# STLINK.net
KiCad netlist of a schematic drawn in Altium Designer
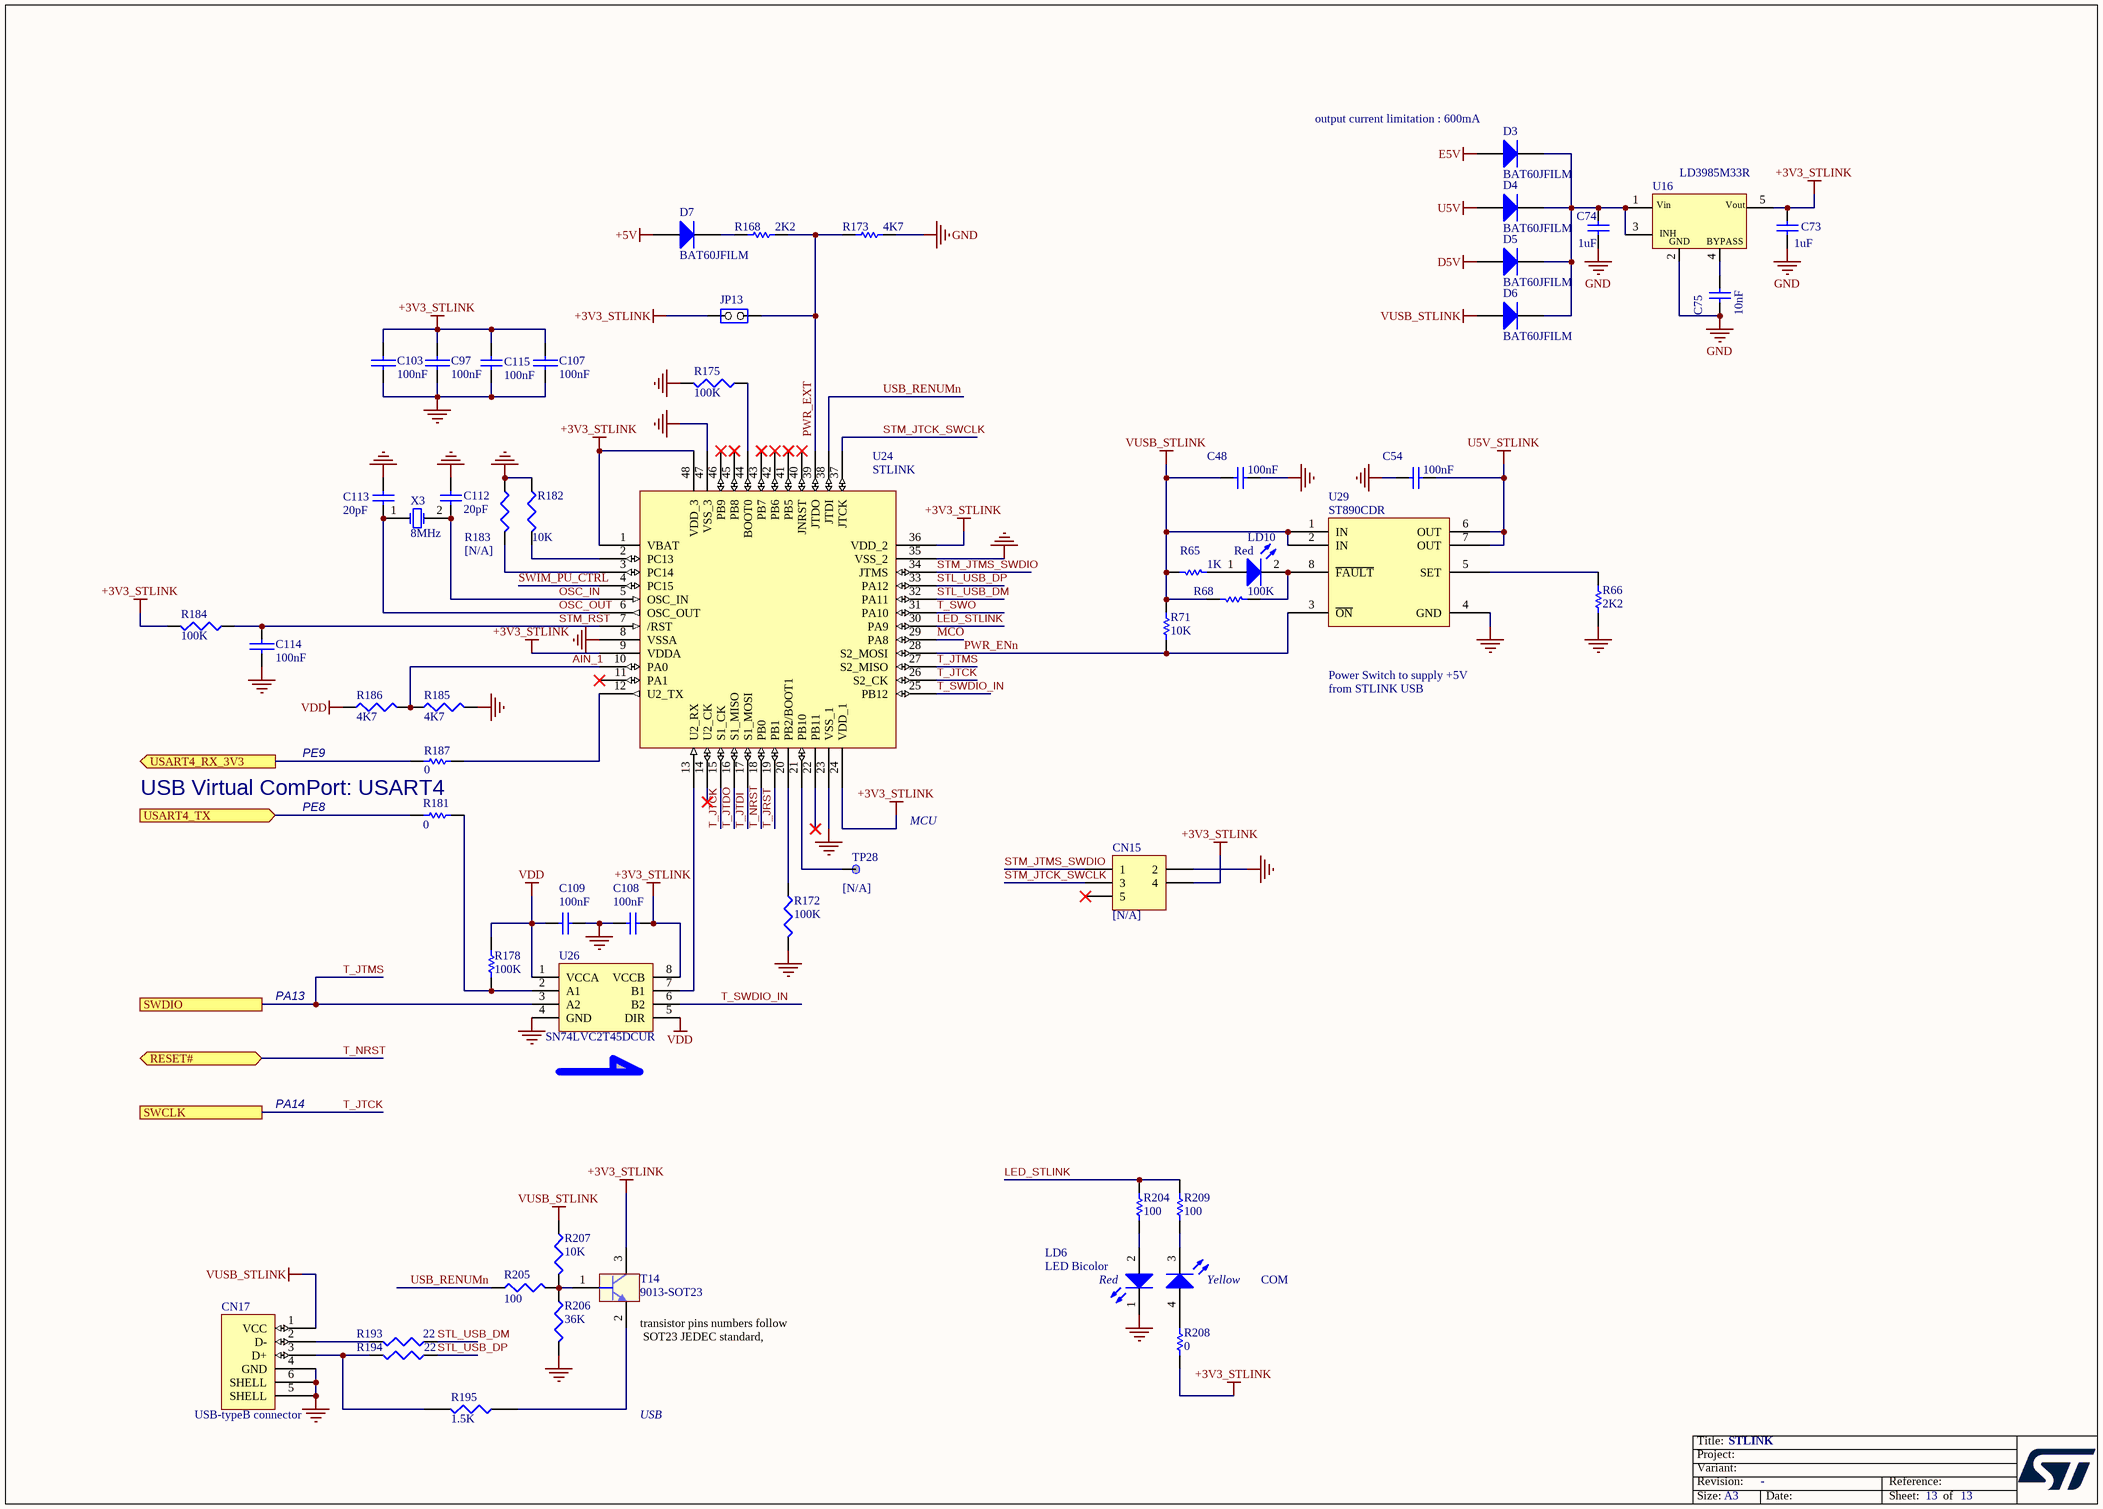
[diagram p0: STLINK.SchDoc]

(export (version "E")
  (design (tool "Eeschema 10.0.6"))
  (components
    (comp (ref "C48")
      (value "100nF")
      (footprint "0402C")
      (description "Capacitor 0402 / 0603 / 0805")
      (libsource (lib "MCD_TOOLS") (part "Capacitor_ST"))
    )
    (comp (ref "C54")
      (value "100nF")
      (footprint "0402C")
      (description "Capacitor 0402 / 0603 / 0805")
      (libsource (lib "MCD_TOOLS") (part "Capacitor_ST"))
    )
    (comp (ref "C73")
      (value "1uF")
      (footprint "0603C")
      (description "Capacitor")
      (fields (field (name "PUBLISHER") "Altium Limited"))
      (libsource (lib "Miscellaneous Devices") (part "CAP"))
    )
    (comp (ref "C74")
      (value "1uF")
      (footprint "0603C")
      (description "Capacitor")
      (fields (field (name "PUBLISHER") "Altium Limited"))
      (libsource (lib "Miscellaneous Devices") (part "CAP"))
    )
    (comp (ref "C75")
      (value "10nF")
      (footprint "0402C")
      (description "Capacitor")
      (fields (field (name "PUBLISHER") "Altium Limited"))
      (libsource (lib "Miscellaneous Devices") (part "Cap"))
    )
    (comp (ref "C97") (value "100nF") (footprint "0402C") (libsource (lib "*") (part "CAP")))
    (comp (ref "C103") (value "100nF") (footprint "0402C") (libsource (lib "*") (part "CAP")))
    (comp (ref "C107") (value "100nF") (footprint "0402C") (libsource (lib "*") (part "CAP")))
    (comp (ref "C108")
      (value "100nF")
      (footprint "0402C")
      (description "Capacitor")
      (fields (field (name "PUBLISHER") "Altium Limited"))
      (libsource (lib "Miscellaneous Devices") (part "CAP"))
    )
    (comp (ref "C109")
      (value "100nF")
      (footprint "0402C")
      (description "Capacitor")
      (fields (field (name "PUBLISHER") "Altium Limited"))
      (libsource (lib "Miscellaneous Devices") (part "CAP"))
    )
    (comp (ref "C112")
      (value "20pF")
      (footprint "0402C")
      (description "Capacitor")
      (fields (field (name "PUBLISHER") "Altium Limited"))
      (libsource (lib "Miscellaneous Devices") (part "CAP"))
    )
    (comp (ref "C113")
      (value "20pF")
      (footprint "0402C")
      (description "Capacitor")
      (fields (field (name "PUBLISHER") "Altium Limited"))
      (libsource (lib "Miscellaneous Devices") (part "CAP"))
    )
    (comp (ref "C114") (value "100nF") (footprint "0402C") (libsource (lib "*") (part "CAP")))
    (comp (ref "C115")
      (value "100nF")
      (footprint "0402C")
      (description "Capacitor")
      (fields (field (name "PUBLISHER") "Altium Limited"))
      (libsource (lib "*") (part "Cap"))
    )
    (comp (ref "CN15")
      (value "[N/A]")
      (footprint "HDR_2X3-1_2R54-6")
      (description "Header, 3-Pin, Dual row")
      (fields (field (name "PUBLISHER") "Altium Limited"))
      (libsource (lib "Miscellaneous Connectors") (part "Header 3X2"))
    )
    (comp (ref "CN17")
      (value "USB-typeB connector")
      (footprint "USB-B")
      (libsource (lib "MB1070") (part "USB-typeB connector"))
    )
    (comp (ref "D3")
      (value "BAT60JFILM")
      (footprint "SOD-323")
      (description "Default Diode")
      (fields (field (name "PUBLISHER") "Altium Limited"))
      (libsource (lib "MB1144_1") (part "Diode"))
    )
    (comp (ref "D4")
      (value "BAT60JFILM")
      (footprint "SOD-323")
      (description "Default Diode")
      (fields (field (name "PUBLISHER") "Altium Limited"))
      (libsource (lib "MB1144_1") (part "Diode"))
    )
    (comp (ref "D5")
      (value "BAT60JFILM")
      (footprint "SOD-323")
      (description "Default Diode")
      (fields (field (name "PUBLISHER") "Altium Limited"))
      (libsource (lib "MB1144_1") (part "Diode"))
    )
    (comp (ref "D6")
      (value "BAT60JFILM")
      (footprint "SOD-323")
      (description "Default Diode")
      (fields (field (name "PUBLISHER") "Altium Limited"))
      (libsource (lib "MB1144_1") (part "Diode"))
    )
    (comp (ref "D7")
      (value "BAT60JFILM")
      (footprint "SOD-323")
      (description "Default Diode")
      (fields (field (name "PUBLISHER") "Altium Limited"))
      (libsource (lib "MB1144_1") (part "Diode"))
    )
    (comp (ref "JP13") (value "~") (footprint "SIP2") (libsource (lib "*") (part "JP2")))
    (comp (ref "LD6")
      (value "LED Bicolor")
      (footprint "LED2_3528")
      (fields (field (name "SILKSCREEN") "COM"))
      (libsource (lib "MB819") (part "HSMF-A201-A00J1"))
    )
    (comp (ref "LD10")
      (value "Red")
      (footprint "0603D")
      (description "Typical RED, GREEN, YELLOW, AMBER GaAs LED")
      (fields (field (name "PUBLISHER") "Altium Limited"))
      (libsource (lib "Miscellaneous Devices") (part "LED2"))
    )
    (comp (ref "R65")
      (value "1K")
      (footprint "0402R")
      (description "Resistor")
      (fields (field (name "PUBLISHER") "Altium Limited"))
      (libsource (lib "*") (part "Res1"))
    )
    (comp (ref "R66")
      (value "2K2")
      (footprint "0402R")
      (description "Resistor")
      (fields (field (name "PUBLISHER") "Altium Limited"))
      (libsource (lib "Miscellaneous Devices") (part "res1"))
    )
    (comp (ref "R68")
      (value "100K")
      (footprint "0402R")
      (description "Resistor")
      (fields (field (name "PUBLISHER") "Altium Limited"))
      (libsource (lib "*") (part "Res1"))
    )
    (comp (ref "R71")
      (value "10K")
      (footprint "0402R")
      (description "Resistor")
      (libsource (lib "MCD_TOOLS") (part "Resistor_ST"))
    )
    (comp (ref "R168")
      (value "2K2")
      (footprint "0402R")
      (description "Resistor")
      (fields (field (name "PUBLISHER") "Altium Limited"))
      (libsource (lib "Miscellaneous Devices") (part "res1"))
    )
    (comp (ref "R172")
      (value "100K")
      (footprint "0402R")
      (description "Resistor")
      (libsource (lib "") (part "RES1_1"))
    )
    (comp (ref "R173")
      (value "4K7")
      (footprint "0402R")
      (description "Resistor")
      (fields (field (name "PUBLISHER") "Altium Limited"))
      (libsource (lib "Miscellaneous Devices") (part "res1"))
    )
    (comp (ref "R175")
      (value "100K")
      (footprint "0402R")
      (description "Resistor")
      (libsource (lib "") (part "RES1_1"))
    )
    (comp (ref "R178")
      (value "100K")
      (footprint "0402R")
      (description "Resistor")
      (fields (field (name "PUBLISHER") "Altium Limited"))
      (libsource (lib "Miscellaneous Devices") (part "Res1"))
    )
    (comp (ref "R181")
      (value "0")
      (footprint "0603R")
      (description "Resistor")
      (fields (field (name "PUBLISHER") "Altium Limited"))
      (libsource (lib "Miscellaneous Devices") (part "Res1"))
    )
    (comp (ref "R182")
      (value "10K")
      (footprint "0402R")
      (description "Resistor")
      (libsource (lib "*") (part "R"))
    )
    (comp (ref "R183") (value "[N/A]") (footprint "0603R") (libsource (lib "*") (part "R")))
    (comp (ref "R184")
      (value "100K")
      (footprint "0402R")
      (description "Resistor")
      (libsource (lib "") (part "RES1_1"))
    )
    (comp (ref "R185") (value "4K7") (footprint "0402R") (libsource (lib "") (part "RES1_1")))
    (comp (ref "R186") (value "4K7") (footprint "0402R") (libsource (lib "") (part "RES1_1")))
    (comp (ref "R187")
      (value "0")
      (footprint "0603R")
      (description "Resistor")
      (fields (field (name "PUBLISHER") "Altium Limited"))
      (libsource (lib "Miscellaneous Devices") (part "Res1"))
    )
    (comp (ref "R193")
      (value "22")
      (footprint "0402R")
      (description "Resistor")
      (libsource (lib "") (part "RES1_1"))
    )
    (comp (ref "R194")
      (value "22")
      (footprint "0402R")
      (description "Resistor")
      (libsource (lib "") (part "RES1_1"))
    )
    (comp (ref "R195") (value "1.5K") (footprint "0402R") (libsource (lib "*") (part "RES1")))
    (comp (ref "R204")
      (value "100")
      (footprint "0402R")
      (description "Resistor")
      (fields (field (name "PUBLISHER") "Altium Limited"))
      (libsource (lib "Miscellaneous Devices") (part "Res1"))
    )
    (comp (ref "R205")
      (value "100")
      (footprint "0402R")
      (description "Resistor")
      (libsource (lib "*") (part "R"))
    )
    (comp (ref "R206")
      (value "36K")
      (footprint "0402R")
      (description "Resistor")
      (libsource (lib "*") (part "R"))
    )
    (comp (ref "R207")
      (value "10K")
      (footprint "0402R")
      (description "Resistor")
      (libsource (lib "*") (part "R"))
    )
    (comp (ref "R208")
      (value "0")
      (footprint "0603R")
      (description "Resistor")
      (fields (field (name "PUBLISHER") "Altium Limited"))
      (libsource (lib "Miscellaneous Devices") (part "Res1"))
    )
    (comp (ref "R209")
      (value "100")
      (footprint "0402R")
      (description "Resistor")
      (fields (field (name "PUBLISHER") "Altium Limited"))
      (libsource (lib "Miscellaneous Devices") (part "Res1"))
    )
    (comp (ref "T14")
      (value "9013-SOT23")
      (footprint "SOT-23")
      (description "NPN Bipolar Transistor")
      (libsource (lib "MCD_TOOLS") (part "9013-SOT23"))
    )
    (comp (ref "TP28") (value "[N/A]") (footprint "TP") (libsource (lib "*") (part "TP")))
    (comp (ref "U16")
      (value "LD3985M33R")
      (footprint "SOT23-5")
      (description "Ultra low drop-low noise BiCMOS voltage, regulators low ESR capacitors compatible")
      (libsource (lib "MCD_TOOLS") (part "LD3985M33R"))
    )
    (comp (ref "U24")
      (value "STLINK")
      (footprint "LQFP48_0R5_9X9")
      (libsource (lib "*") (part "STM32F10x(48pin)"))
    )
    (comp (ref "U26")
      (value "SN74LVC2T45DCUR")
      (footprint "USOP8_0R5_2X3R1")
      (libsource (lib "MB818") (part "SN74LVC2T45DCUT"))
    )
    (comp (ref "U29")
      (value "ST890CDR")
      (footprint "SOIC8_1R27_4R9X6")
      (libsource (lib "MB1167") (part "ST890CDR"))
    )
    (comp (ref "X3")
      (value "8MHz")
      (footprint "XTAL_2SM_12R7X4R7")
      (description "Crystal Oscillator")
      (fields (field (name "PUBLISHER") "Altium Limited"))
      (libsource (lib "*") (part "XTAL"))
    )
  )
  (nets
    (net (code "1") (name "+3V3_STLINK") (class "Default")
      (node (ref "C103") (pin "2") (pinfunction "2_2") (pintype "passive"))
      (node (ref "C107") (pin "2") (pinfunction "2_2") (pintype "passive"))
      (node (ref "C108") (pin "1") (pinfunction "1_1") (pintype "passive"))
      (node (ref "C115") (pin "1") (pinfunction "1_1") (pintype "passive"))
      (node (ref "C73") (pin "1") (pinfunction "1_1") (pintype "passive"))
      (node (ref "C97") (pin "2") (pinfunction "2_2") (pintype "passive"))
      (node (ref "CN15") (pin "4") (pinfunction "4_4") (pintype "passive"))
      (node (ref "JP13") (pin "1") (pinfunction "COMMON_1") (pintype "passive"))
      (node (ref "R184") (pin "2") (pinfunction "2_2") (pintype "passive"))
      (node (ref "R208") (pin "2") (pinfunction "2_2") (pintype "passive"))
      (node (ref "T14") (pin "3") (pinfunction "C_3") (pintype "passive"))
      (node (ref "U16") (pin "5") (pinfunction "Vout_5") (pintype "passive"))
      (node (ref "U24") (pin "1") (pinfunction "VBAT_1") (pintype "power_in"))
      (node (ref "U24") (pin "24") (pinfunction "VDD_1_24") (pintype "power_in"))
      (node (ref "U24") (pin "36") (pinfunction "VDD_2_36") (pintype "power_in"))
      (node (ref "U24") (pin "48") (pinfunction "VDD_3_48") (pintype "power_in"))
      (node (ref "U24") (pin "9") (pinfunction "VDDA_9") (pintype "power_in"))
      (node (ref "U26") (pin "8") (pinfunction "VCCB_8") (pintype "passive"))
    )
    (net (code "2") (name "+5V") (class "Default")
      (node (ref "D7") (pin "1") (pinfunction "A_1") (pintype "passive"))
    )
    (net (code "3") (name "/AIN_1") (class "Default")
      (node (ref "R185") (pin "1") (pinfunction "1_1") (pintype "passive"))
      (node (ref "R186") (pin "2") (pinfunction "2_2") (pintype "passive"))
      (node (ref "U24") (pin "10") (pinfunction "PA0_10") (pintype "bidirectional"))
    )
    (net (code "4") (name "/LED_STLINK") (class "Default")
      (node (ref "R204") (pin "1") (pinfunction "1_1") (pintype "passive"))
      (node (ref "R209") (pin "1") (pinfunction "1_1") (pintype "passive"))
      (node (ref "U24") (pin "30") (pinfunction "PA9_30") (pintype "bidirectional"))
    )
    (net (code "5") (name "/MCO") (class "Default")
      (node (ref "U24") (pin "29") (pinfunction "PA8_29") (pintype "bidirectional"))
    )
    (net (code "6") (name "/OSC_IN") (class "Default")
      (node (ref "C112") (pin "2") (pinfunction "2_2") (pintype "passive"))
      (node (ref "U24") (pin "5") (pinfunction "OSC_IN_5") (pintype "input"))
      (node (ref "X3") (pin "2") (pinfunction "OSC2_2") (pintype "passive"))
    )
    (net (code "7") (name "/OSC_OUT") (class "Default")
      (node (ref "C113") (pin "2") (pinfunction "2_2") (pintype "passive"))
      (node (ref "U24") (pin "6") (pinfunction "OSC_OUT_6") (pintype "output"))
      (node (ref "X3") (pin "1") (pinfunction "OSC1_1") (pintype "passive"))
    )
    (net (code "8") (name "/PWR_ENn") (class "Default")
      (node (ref "R71") (pin "1") (pinfunction "1_1") (pintype "passive"))
      (node (ref "U24") (pin "28") (pinfunction "S2_MOSI_28") (pintype "bidirectional"))
      (node (ref "U29") (pin "3") (pinfunction "~{ON}_3") (pintype "passive"))
    )
    (net (code "9") (name "/PWR_EXT") (class "Default")
      (node (ref "JP13") (pin "2") (pinfunction "NO_2") (pintype "passive"))
      (node (ref "R168") (pin "1") (pinfunction "1_1") (pintype "passive"))
      (node (ref "R173") (pin "2") (pinfunction "2_2") (pintype "passive"))
      (node (ref "U24") (pin "39") (pinfunction "JTDO_39") (pintype "bidirectional"))
    )
    (net (code "10") (name "/STL_USB_DM") (class "Default")
      (node (ref "R193") (pin "1") (pinfunction "1_1") (pintype "passive"))
      (node (ref "U24") (pin "32") (pinfunction "PA11_32") (pintype "bidirectional"))
    )
    (net (code "11") (name "/STL_USB_DP") (class "Default")
      (node (ref "R194") (pin "1") (pinfunction "1_1") (pintype "passive"))
      (node (ref "U24") (pin "33") (pinfunction "PA12_33") (pintype "bidirectional"))
    )
    (net (code "12") (name "/STM_JTCK_SWCLK") (class "Default")
      (node (ref "CN15") (pin "3") (pinfunction "3_3") (pintype "passive"))
      (node (ref "U24") (pin "37") (pinfunction "JTCK_37") (pintype "bidirectional"))
    )
    (net (code "13") (name "/STM_JTMS_SWDIO") (class "Default")
      (node (ref "CN15") (pin "1") (pinfunction "1_1") (pintype "passive"))
      (node (ref "U24") (pin "34") (pinfunction "JTMS_34") (pintype "bidirectional"))
    )
    (net (code "14") (name "/STM_RST") (class "Default")
      (node (ref "C114") (pin "2") (pinfunction "2_2") (pintype "passive"))
      (node (ref "R184") (pin "1") (pinfunction "1_1") (pintype "passive"))
      (node (ref "U24") (pin "7") (pinfunction "/RST_7") (pintype "input"))
    )
    (net (code "15") (name "/SWIM_PU_CTRL") (class "Default")
      (node (ref "U24") (pin "4") (pinfunction "PC15_4") (pintype "bidirectional"))
    )
    (net (code "16") (name "/T_JRST") (class "Default")
      (node (ref "U24") (pin "19") (pinfunction "PB1_19") (pintype "bidirectional"))
    )
    (net (code "17") (name "/T_JTCK") (class "Default")
      (node (ref "U24") (pin "15") (pinfunction "S1_CK_15") (pintype "bidirectional"))
      (node (ref "U24") (pin "26") (pinfunction "S2_CK_26") (pintype "bidirectional"))
    )
    (net (code "18") (name "/T_JTDI") (class "Default")
      (node (ref "U24") (pin "17") (pinfunction "S1_MOSI_17") (pintype "bidirectional"))
    )
    (net (code "19") (name "/T_JTDO") (class "Default")
      (node (ref "U24") (pin "16") (pinfunction "S1_MISO_16") (pintype "bidirectional"))
    )
    (net (code "20") (name "/T_JTMS") (class "Default")
      (node (ref "U24") (pin "27") (pinfunction "S2_MISO_27") (pintype "bidirectional"))
      (node (ref "U26") (pin "3") (pinfunction "A2_3") (pintype "passive"))
    )
    (net (code "21") (name "/T_NRST") (class "Default")
      (node (ref "U24") (pin "18") (pinfunction "PB0_18") (pintype "bidirectional"))
    )
    (net (code "22") (name "/T_SWDIO_IN") (class "Default")
      (node (ref "U24") (pin "25") (pinfunction "PB12_25") (pintype "bidirectional"))
      (node (ref "U26") (pin "6") (pinfunction "B2_6") (pintype "passive"))
    )
    (net (code "23") (name "/T_SWO") (class "Default")
      (node (ref "U24") (pin "31") (pinfunction "PA10_31") (pintype "bidirectional"))
    )
    (net (code "24") (name "/USART4_RX_3V3") (class "Default")
      (node (ref "R187") (pin "2") (pinfunction "2_2") (pintype "passive"))
    )
    (net (code "25") (name "/USART4_TX") (class "Default")
      (node (ref "R181") (pin "1") (pinfunction "1_1") (pintype "passive"))
    )
    (net (code "26") (name "/USB_RENUMn") (class "Default")
      (node (ref "R205") (pin "1") (pinfunction "1_1") (pintype "passive"))
      (node (ref "U24") (pin "38") (pinfunction "JTDI_38") (pintype "bidirectional"))
    )
    (net (code "27") (name "D5V") (class "Default")
      (node (ref "D5") (pin "1") (pinfunction "A_1") (pintype "passive"))
    )
    (net (code "28") (name "E5V") (class "Default")
      (node (ref "D3") (pin "1") (pinfunction "A_1") (pintype "passive"))
    )
    (net (code "29") (name "GND") (class "Default")
      (node (ref "C103") (pin "1") (pinfunction "1_1") (pintype "passive"))
      (node (ref "C107") (pin "1") (pinfunction "1_1") (pintype "passive"))
      (node (ref "C108") (pin "2") (pinfunction "2_2") (pintype "passive"))
      (node (ref "C109") (pin "2") (pinfunction "2_2") (pintype "passive"))
      (node (ref "C112") (pin "1") (pinfunction "1_1") (pintype "passive"))
      (node (ref "C113") (pin "1") (pinfunction "1_1") (pintype "passive"))
      (node (ref "C114") (pin "1") (pinfunction "1_1") (pintype "passive"))
      (node (ref "C115") (pin "2") (pinfunction "2_2") (pintype "passive"))
      (node (ref "C48") (pin "2") (pinfunction "2_2") (pintype "passive"))
      (node (ref "C54") (pin "1") (pinfunction "1_1") (pintype "passive"))
      (node (ref "C73") (pin "2") (pinfunction "2_2") (pintype "passive"))
      (node (ref "C74") (pin "2") (pinfunction "2_2") (pintype "passive"))
      (node (ref "C75") (pin "2") (pinfunction "2_2") (pintype "passive"))
      (node (ref "C97") (pin "1") (pinfunction "1_1") (pintype "passive"))
      (node (ref "CN15") (pin "2") (pinfunction "2_2") (pintype "passive"))
      (node (ref "CN17") (pin "4") (pinfunction "GND_4") (pintype "passive"))
      (node (ref "CN17") (pin "5") (pinfunction "SHELL_5") (pintype "power_in"))
      (node (ref "CN17") (pin "6") (pinfunction "SHELL_6") (pintype "power_in"))
      (node (ref "LD6") (pin "1") (pinfunction "RED_cathode_1") (pintype "passive"))
      (node (ref "R172") (pin "2") (pinfunction "2_2") (pintype "passive"))
      (node (ref "R173") (pin "1") (pinfunction "1_1") (pintype "passive"))
      (node (ref "R175") (pin "2") (pinfunction "2_2") (pintype "passive"))
      (node (ref "R182") (pin "1") (pinfunction "1_1") (pintype "passive"))
      (node (ref "R183") (pin "1") (pinfunction "1_1") (pintype "passive"))
      (node (ref "R185") (pin "2") (pinfunction "2_2") (pintype "passive"))
      (node (ref "R206") (pin "2") (pinfunction "2_2") (pintype "passive"))
      (node (ref "R66") (pin "2") (pinfunction "2_2") (pintype "passive"))
      (node (ref "U16") (pin "2") (pinfunction "GND_2") (pintype "passive"))
      (node (ref "U24") (pin "23") (pinfunction "VSS_1_23") (pintype "passive"))
      (node (ref "U24") (pin "35") (pinfunction "VSS_2_35") (pintype "passive"))
      (node (ref "U24") (pin "47") (pinfunction "VSS_3_47") (pintype "passive"))
      (node (ref "U24") (pin "8") (pinfunction "VSSA_8") (pintype "passive"))
      (node (ref "U26") (pin "4") (pinfunction "GND_4") (pintype "passive"))
      (node (ref "U29") (pin "4") (pinfunction "GND_4") (pintype "passive"))
    )
    (net (code "30") (name "Net-(CN17-D+)") (class "Default")
      (node (ref "CN17") (pin "3") (pinfunction "D+_3") (pintype "bidirectional"))
      (node (ref "R194") (pin "2") (pinfunction "2_2") (pintype "passive"))
      (node (ref "R195") (pin "2") (pinfunction "2_2") (pintype "passive"))
    )
    (net (code "31") (name "Net-(CN17-D-)") (class "Default")
      (node (ref "CN17") (pin "2") (pinfunction "D-_2") (pintype "bidirectional"))
      (node (ref "R193") (pin "2") (pinfunction "2_2") (pintype "passive"))
    )
    (net (code "32") (name "Net-(D3-K)") (class "Default")
      (node (ref "C74") (pin "1") (pinfunction "1_1") (pintype "passive"))
      (node (ref "D3") (pin "2") (pinfunction "K_2") (pintype "passive"))
      (node (ref "D4") (pin "2") (pinfunction "K_2") (pintype "passive"))
      (node (ref "D5") (pin "2") (pinfunction "K_2") (pintype "passive"))
      (node (ref "D6") (pin "2") (pinfunction "K_2") (pintype "passive"))
      (node (ref "U16") (pin "1") (pinfunction "Vin_1") (pintype "passive"))
      (node (ref "U16") (pin "3") (pinfunction "CE_3") (pintype "passive"))
    )
    (net (code "33") (name "Net-(D7-K)") (class "Default")
      (node (ref "D7") (pin "2") (pinfunction "K_2") (pintype "passive"))
      (node (ref "R168") (pin "2") (pinfunction "2_2") (pintype "passive"))
    )
    (net (code "34") (name "Net-(LD6-Red_anode)") (class "Default")
      (node (ref "LD6") (pin "2") (pinfunction "Red_anode_2") (pintype "passive"))
      (node (ref "R204") (pin "2") (pinfunction "2_2") (pintype "passive"))
    )
    (net (code "35") (name "Net-(LD6-YellowGreen_anode)") (class "Default")
      (node (ref "LD6") (pin "4") (pinfunction "YellowGreen_anode_4") (pintype "passive"))
      (node (ref "R208") (pin "1") (pinfunction "1_1") (pintype "passive"))
    )
    (net (code "36") (name "Net-(LD6-YellowGreen_cathode)") (class "Default")
      (node (ref "LD6") (pin "3") (pinfunction "YellowGreen_cathode_3") (pintype "passive"))
      (node (ref "R209") (pin "2") (pinfunction "2_2") (pintype "passive"))
    )
    (net (code "37") (name "Net-(LD10-A)") (class "Default")
      (node (ref "LD10") (pin "1") (pinfunction "A_1") (pintype "passive"))
      (node (ref "R65") (pin "2") (pinfunction "2_2") (pintype "passive"))
    )
    (net (code "38") (name "Net-(LD10-K)") (class "Default")
      (node (ref "LD10") (pin "2") (pinfunction "K_2") (pintype "passive"))
      (node (ref "R68") (pin "2") (pinfunction "2_2") (pintype "passive"))
      (node (ref "U29") (pin "8") (pinfunction "~{FAULT}_8") (pintype "passive"))
    )
    (net (code "39") (name "Net-(T14-B)") (class "Default")
      (node (ref "R205") (pin "2") (pinfunction "2_2") (pintype "passive"))
      (node (ref "R206") (pin "1") (pinfunction "1_1") (pintype "passive"))
      (node (ref "R207") (pin "2") (pinfunction "2_2") (pintype "passive"))
      (node (ref "T14") (pin "1") (pinfunction "B_1") (pintype "passive"))
    )
    (net (code "40") (name "Net-(T14-E)") (class "Default")
      (node (ref "R195") (pin "1") (pinfunction "1_1") (pintype "passive"))
      (node (ref "T14") (pin "2") (pinfunction "E_2") (pintype "passive"))
    )
    (net (code "41") (name "Net-(U16-BYPASS)") (class "Default")
      (node (ref "C75") (pin "1") (pinfunction "1_1") (pintype "passive"))
      (node (ref "U16") (pin "4") (pinfunction "BYPASS_4") (pintype "passive"))
    )
    (net (code "42") (name "Net-(U24-BOOT0)") (class "Default")
      (node (ref "R175") (pin "1") (pinfunction "1_1") (pintype "passive"))
      (node (ref "U24") (pin "44") (pinfunction "BOOT0_44") (pintype "bidirectional"))
    )
    (net (code "43") (name "Net-(U24-PB2{slash}BOOT1)") (class "Default")
      (node (ref "R172") (pin "1") (pinfunction "1_1") (pintype "passive"))
      (node (ref "U24") (pin "20") (pinfunction "PB2/BOOT1_20") (pintype "passive"))
    )
    (net (code "44") (name "Net-(U24-PB10)") (class "Default")
      (node (ref "TP28") (pin "1") (pinfunction "1_1") (pintype "passive"))
      (node (ref "U24") (pin "21") (pinfunction "PB10_21") (pintype "bidirectional"))
    )
    (net (code "45") (name "Net-(U24-PC13)") (class "Default")
      (node (ref "R182") (pin "2") (pinfunction "2_2") (pintype "passive"))
      (node (ref "U24") (pin "2") (pinfunction "PC13_2") (pintype "bidirectional"))
    )
    (net (code "46") (name "Net-(U24-PC14)") (class "Default")
      (node (ref "R183") (pin "2") (pinfunction "2_2") (pintype "passive"))
      (node (ref "U24") (pin "3") (pinfunction "PC14_3") (pintype "bidirectional"))
    )
    (net (code "47") (name "Net-(U24-U2_RX)") (class "Default")
      (node (ref "U24") (pin "13") (pinfunction "U2_RX_13") (pintype "input"))
      (node (ref "U26") (pin "7") (pinfunction "B1_7") (pintype "passive"))
    )
    (net (code "48") (name "Net-(U24-U2_TX)") (class "Default")
      (node (ref "R187") (pin "1") (pinfunction "1_1") (pintype "passive"))
      (node (ref "U24") (pin "12") (pinfunction "U2_TX_12") (pintype "output"))
    )
    (net (code "49") (name "Net-(U26-A1)") (class "Default")
      (node (ref "R178") (pin "2") (pinfunction "2_2") (pintype "passive"))
      (node (ref "R181") (pin "2") (pinfunction "2_2") (pintype "passive"))
      (node (ref "U26") (pin "2") (pinfunction "A1_2") (pintype "passive"))
    )
    (net (code "50") (name "Net-(U29-SET)") (class "Default")
      (node (ref "R66") (pin "1") (pinfunction "1_1") (pintype "passive"))
      (node (ref "U29") (pin "5") (pinfunction "SET_5") (pintype "passive"))
    )
    (net (code "51") (name "U5V") (class "Default")
      (node (ref "D4") (pin "1") (pinfunction "A_1") (pintype "passive"))
    )
    (net (code "52") (name "U5V_STLINK") (class "Default")
      (node (ref "C54") (pin "2") (pinfunction "2_2") (pintype "passive"))
      (node (ref "U29") (pin "6") (pinfunction "OUT_6") (pintype "passive"))
      (node (ref "U29") (pin "7") (pinfunction "OUT_7") (pintype "passive"))
    )
    (net (code "53") (name "VDD") (class "Default")
      (node (ref "C109") (pin "1") (pinfunction "1_1") (pintype "passive"))
      (node (ref "R178") (pin "1") (pinfunction "1_1") (pintype "passive"))
      (node (ref "R186") (pin "1") (pinfunction "1_1") (pintype "passive"))
      (node (ref "U26") (pin "1") (pinfunction "VCCA_1") (pintype "passive"))
      (node (ref "U26") (pin "5") (pinfunction "DIR_5") (pintype "passive"))
    )
    (net (code "54") (name "VUSB_STLINK") (class "Default")
      (node (ref "C48") (pin "1") (pinfunction "1_1") (pintype "passive"))
      (node (ref "CN17") (pin "1") (pinfunction "VCC_1") (pintype "bidirectional"))
      (node (ref "D6") (pin "1") (pinfunction "A_1") (pintype "passive"))
      (node (ref "R207") (pin "1") (pinfunction "1_1") (pintype "passive"))
      (node (ref "R65") (pin "1") (pinfunction "1_1") (pintype "passive"))
      (node (ref "R68") (pin "1") (pinfunction "1_1") (pintype "passive"))
      (node (ref "R71") (pin "2") (pinfunction "2_2") (pintype "passive"))
      (node (ref "U29") (pin "1") (pinfunction "IN_1") (pintype "passive"))
      (node (ref "U29") (pin "2") (pinfunction "IN_2") (pintype "passive"))
    )
    (net (code "55") (name "unconnected-(CN15-Pad5)") (class "Default")
      (node (ref "CN15") (pin "5") (pinfunction "5_5") (pintype "passive+no_connect"))
    )
    (net (code "56") (name "unconnected-(U24-JNRST-Pad40)") (class "Default")
      (node (ref "U24") (pin "40") (pinfunction "JNRST_40") (pintype "bidirectional+no_connect"))
    )
    (net (code "57") (name "unconnected-(U24-PA1-Pad11)") (class "Default")
      (node (ref "U24") (pin "11") (pinfunction "PA1_11") (pintype "bidirectional+no_connect"))
    )
    (net (code "58") (name "unconnected-(U24-PB5-Pad41)") (class "Default")
      (node (ref "U24") (pin "41") (pinfunction "PB5_41") (pintype "bidirectional+no_connect"))
    )
    (net (code "59") (name "unconnected-(U24-PB6-Pad42)") (class "Default")
      (node (ref "U24") (pin "42") (pinfunction "PB6_42") (pintype "bidirectional+no_connect"))
    )
    (net (code "60") (name "unconnected-(U24-PB7-Pad43)") (class "Default")
      (node (ref "U24") (pin "43") (pinfunction "PB7_43") (pintype "bidirectional+no_connect"))
    )
    (net (code "61") (name "unconnected-(U24-PB8-Pad45)") (class "Default")
      (node (ref "U24") (pin "45") (pinfunction "PB8_45") (pintype "bidirectional+no_connect"))
    )
    (net (code "62") (name "unconnected-(U24-PB9-Pad46)") (class "Default")
      (node (ref "U24") (pin "46") (pinfunction "PB9_46") (pintype "bidirectional+no_connect"))
    )
    (net (code "63") (name "unconnected-(U24-PB11-Pad22)") (class "Default")
      (node (ref "U24") (pin "22") (pinfunction "PB11_22") (pintype "passive+no_connect"))
    )
    (net (code "64") (name "unconnected-(U24-U2_CK-Pad14)") (class "Default")
      (node (ref "U24") (pin "14") (pinfunction "U2_CK_14") (pintype "bidirectional+no_connect"))
    )
  )
)
